# rainforest.net
KiCad netlist of a schematic drawn in EAGLE
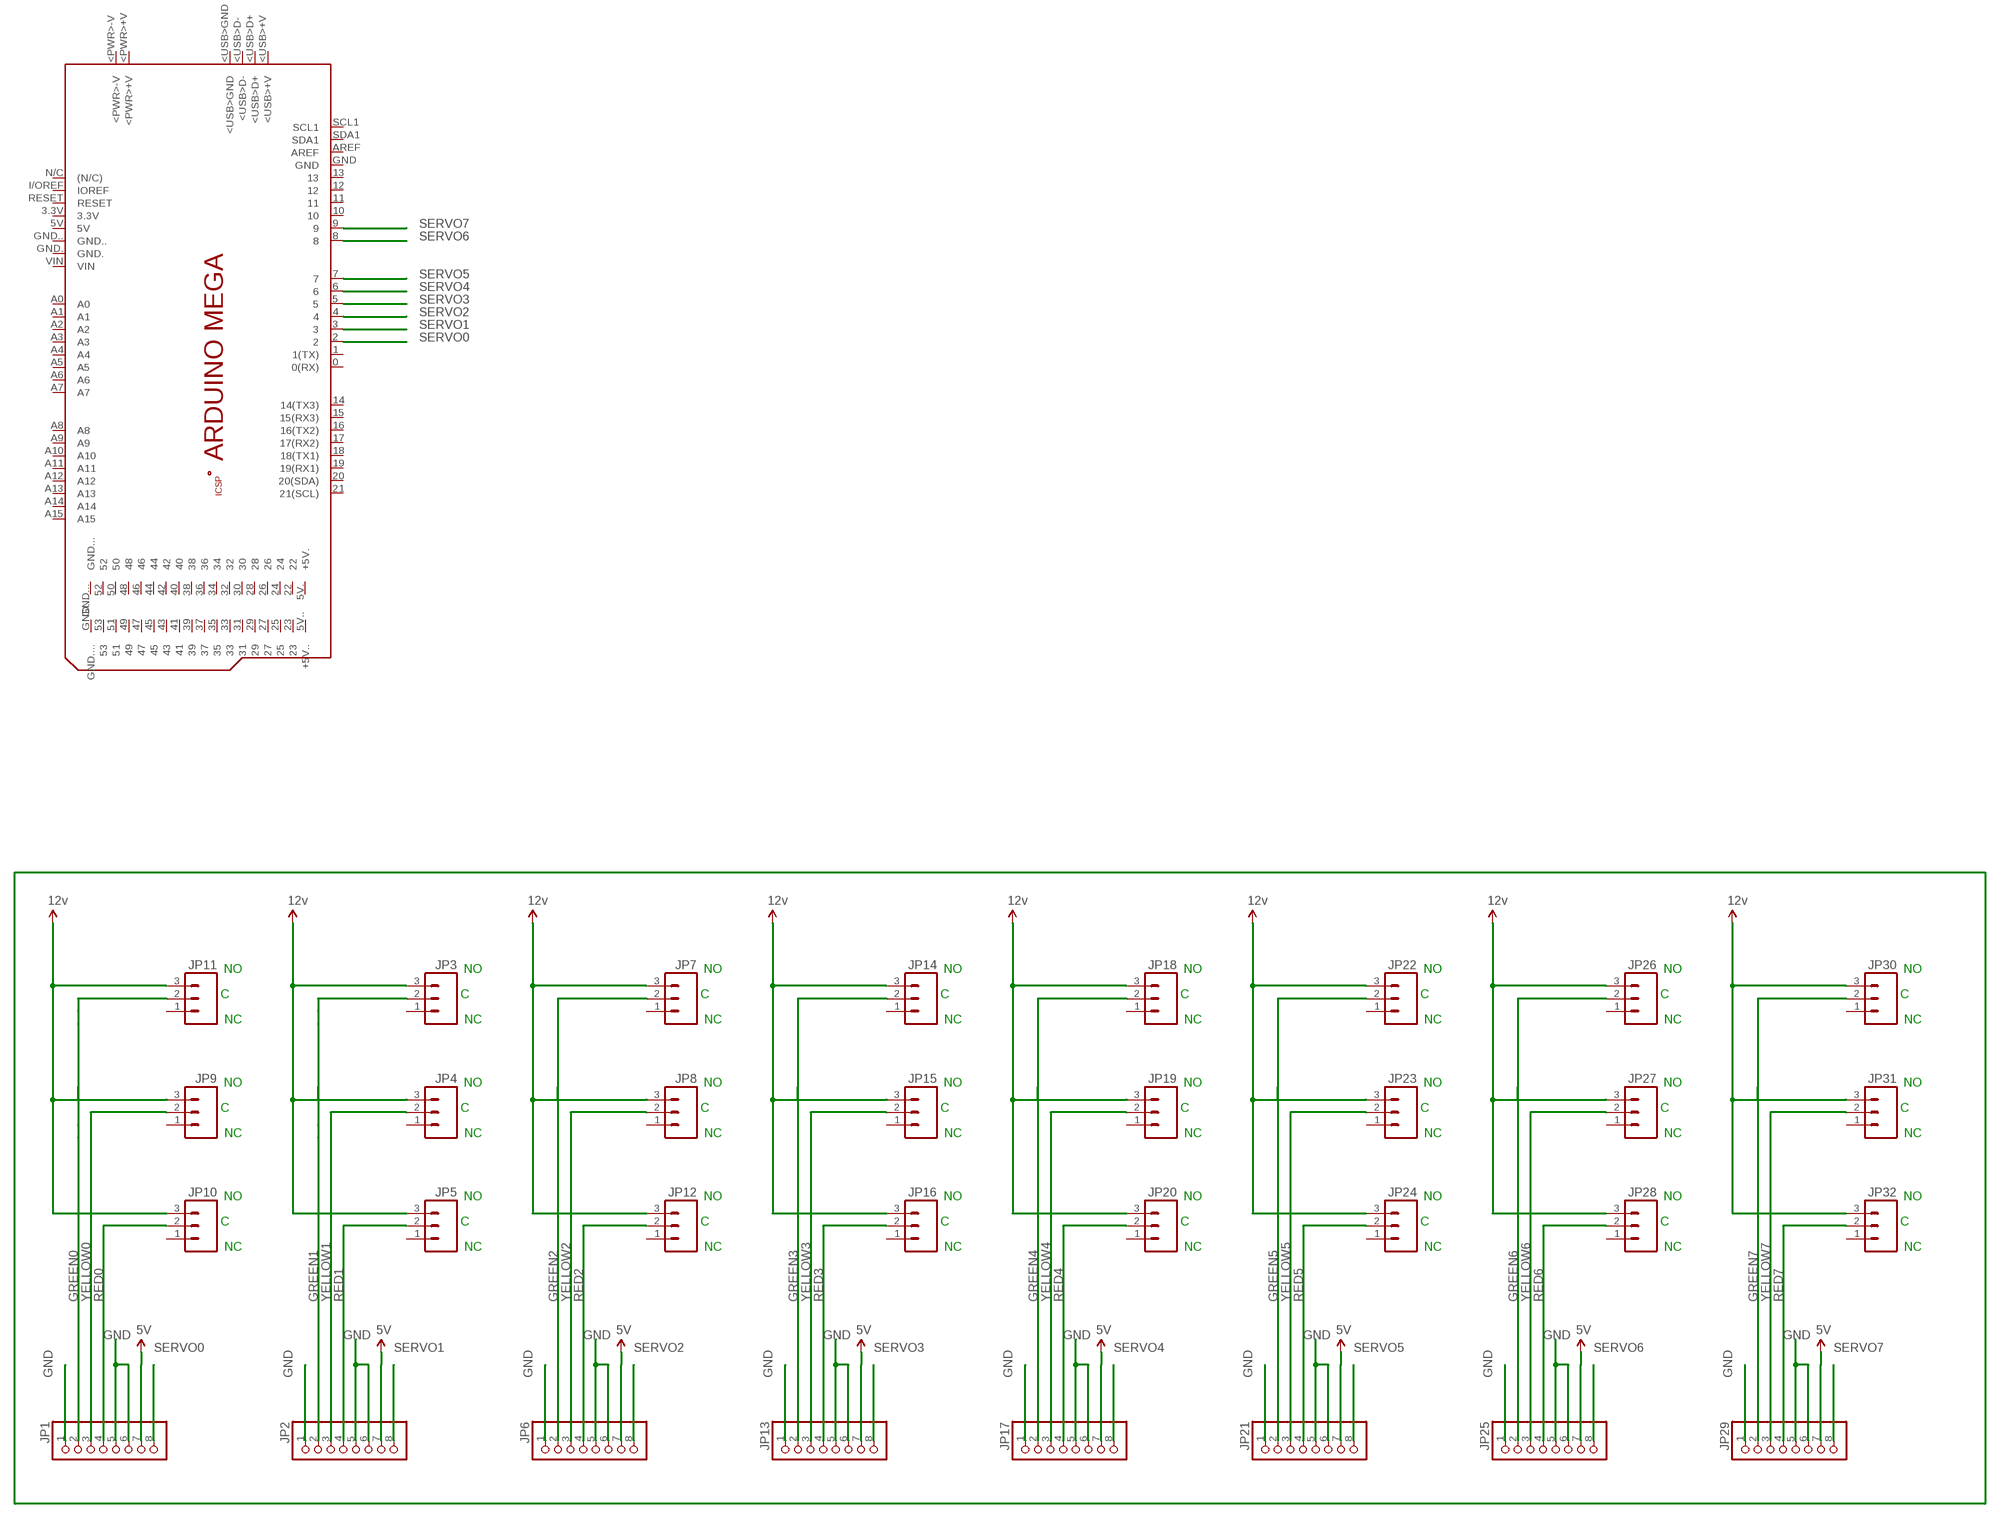
[diagram p0: schematic, sheet 1]

(export (version "E")
  (design (tool "Eeschema 10.0.6"))
  (components
    (comp (ref "JP1")
      (value "PINHD-1X8")
      (footprint "eagle-import:1X08")
      (fields (field (name "PARTNUMBER") "965"))
      (libsource (lib "eagle-import") (part "PINHD-1X8"))
    )
    (comp (ref "JP2")
      (value "PINHD-1X8")
      (footprint "eagle-import:1X08")
      (fields (field (name "PARTNUMBER") "965"))
      (libsource (lib "eagle-import") (part "PINHD-1X8"))
    )
    (comp (ref "JP3")
      (value "M03PTH")
      (footprint "eagle-import:1X03")
      (libsource (lib "eagle-import") (part "M03PTH"))
    )
    (comp (ref "JP4")
      (value "M03PTH")
      (footprint "eagle-import:1X03")
      (libsource (lib "eagle-import") (part "M03PTH"))
    )
    (comp (ref "JP5")
      (value "M03PTH")
      (footprint "eagle-import:1X03")
      (libsource (lib "eagle-import") (part "M03PTH"))
    )
    (comp (ref "JP6")
      (value "PINHD-1X8")
      (footprint "eagle-import:1X08")
      (fields (field (name "PARTNUMBER") "965"))
      (libsource (lib "eagle-import") (part "PINHD-1X8"))
    )
    (comp (ref "JP7")
      (value "M03PTH")
      (footprint "eagle-import:1X03")
      (libsource (lib "eagle-import") (part "M03PTH"))
    )
    (comp (ref "JP8")
      (value "M03PTH")
      (footprint "eagle-import:1X03")
      (libsource (lib "eagle-import") (part "M03PTH"))
    )
    (comp (ref "JP9")
      (value "M03PTH")
      (footprint "eagle-import:1X03")
      (libsource (lib "eagle-import") (part "M03PTH"))
    )
    (comp (ref "JP10")
      (value "M03PTH")
      (footprint "eagle-import:1X03")
      (libsource (lib "eagle-import") (part "M03PTH"))
    )
    (comp (ref "JP11")
      (value "M03PTH")
      (footprint "eagle-import:1X03")
      (libsource (lib "eagle-import") (part "M03PTH"))
    )
    (comp (ref "JP12")
      (value "M03PTH")
      (footprint "eagle-import:1X03")
      (libsource (lib "eagle-import") (part "M03PTH"))
    )
    (comp (ref "JP13")
      (value "PINHD-1X8")
      (footprint "eagle-import:1X08")
      (fields (field (name "PARTNUMBER") "965"))
      (libsource (lib "eagle-import") (part "PINHD-1X8"))
    )
    (comp (ref "JP14")
      (value "M03PTH")
      (footprint "eagle-import:1X03")
      (libsource (lib "eagle-import") (part "M03PTH"))
    )
    (comp (ref "JP15")
      (value "M03PTH")
      (footprint "eagle-import:1X03")
      (libsource (lib "eagle-import") (part "M03PTH"))
    )
    (comp (ref "JP16")
      (value "M03PTH")
      (footprint "eagle-import:1X03")
      (libsource (lib "eagle-import") (part "M03PTH"))
    )
    (comp (ref "JP17")
      (value "PINHD-1X8")
      (footprint "eagle-import:1X08")
      (fields (field (name "PARTNUMBER") "965"))
      (libsource (lib "eagle-import") (part "PINHD-1X8"))
    )
    (comp (ref "JP18")
      (value "M03PTH")
      (footprint "eagle-import:1X03")
      (libsource (lib "eagle-import") (part "M03PTH"))
    )
    (comp (ref "JP19")
      (value "M03PTH")
      (footprint "eagle-import:1X03")
      (libsource (lib "eagle-import") (part "M03PTH"))
    )
    (comp (ref "JP20")
      (value "M03PTH")
      (footprint "eagle-import:1X03")
      (libsource (lib "eagle-import") (part "M03PTH"))
    )
    (comp (ref "JP21")
      (value "PINHD-1X8")
      (footprint "eagle-import:1X08")
      (fields (field (name "PARTNUMBER") "965"))
      (libsource (lib "eagle-import") (part "PINHD-1X8"))
    )
    (comp (ref "JP22")
      (value "M03PTH")
      (footprint "eagle-import:1X03")
      (libsource (lib "eagle-import") (part "M03PTH"))
    )
    (comp (ref "JP23")
      (value "M03PTH")
      (footprint "eagle-import:1X03")
      (libsource (lib "eagle-import") (part "M03PTH"))
    )
    (comp (ref "JP24")
      (value "M03PTH")
      (footprint "eagle-import:1X03")
      (libsource (lib "eagle-import") (part "M03PTH"))
    )
    (comp (ref "JP25")
      (value "PINHD-1X8")
      (footprint "eagle-import:1X08")
      (fields (field (name "PARTNUMBER") "965"))
      (libsource (lib "eagle-import") (part "PINHD-1X8"))
    )
    (comp (ref "JP26")
      (value "M03PTH")
      (footprint "eagle-import:1X03")
      (libsource (lib "eagle-import") (part "M03PTH"))
    )
    (comp (ref "JP27")
      (value "M03PTH")
      (footprint "eagle-import:1X03")
      (libsource (lib "eagle-import") (part "M03PTH"))
    )
    (comp (ref "JP28")
      (value "M03PTH")
      (footprint "eagle-import:1X03")
      (libsource (lib "eagle-import") (part "M03PTH"))
    )
    (comp (ref "JP29")
      (value "PINHD-1X8")
      (footprint "eagle-import:1X08")
      (fields (field (name "PARTNUMBER") "965"))
      (libsource (lib "eagle-import") (part "PINHD-1X8"))
    )
    (comp (ref "JP30")
      (value "M03PTH")
      (footprint "eagle-import:1X03")
      (libsource (lib "eagle-import") (part "M03PTH"))
    )
    (comp (ref "JP31")
      (value "M03PTH")
      (footprint "eagle-import:1X03")
      (libsource (lib "eagle-import") (part "M03PTH"))
    )
    (comp (ref "JP32")
      (value "M03PTH")
      (footprint "eagle-import:1X03")
      (libsource (lib "eagle-import") (part "M03PTH"))
    )
    (comp (ref "PCB1")
      (value "ARDUINO_MEGA")
      (footprint "eagle-import:ARDUINO_MEGA")
      (libsource (lib "eagle-import") (part "ARDUINO_MEGA"))
    )
  )
  (nets
    (net (code "1") (name "/GND") (class "Default")
      (node (ref "JP1") (pin "1") (pinfunction "1_1") (pintype "passive"))
      (node (ref "JP1") (pin "5") (pinfunction "5_5") (pintype "passive"))
      (node (ref "JP1") (pin "6") (pinfunction "6_6") (pintype "passive"))
      (node (ref "JP13") (pin "1") (pinfunction "1_1") (pintype "passive"))
      (node (ref "JP13") (pin "5") (pinfunction "5_5") (pintype "passive"))
      (node (ref "JP13") (pin "6") (pinfunction "6_6") (pintype "passive"))
      (node (ref "JP17") (pin "1") (pinfunction "1_1") (pintype "passive"))
      (node (ref "JP17") (pin "5") (pinfunction "5_5") (pintype "passive"))
      (node (ref "JP17") (pin "6") (pinfunction "6_6") (pintype "passive"))
      (node (ref "JP2") (pin "1") (pinfunction "1_1") (pintype "passive"))
      (node (ref "JP2") (pin "5") (pinfunction "5_5") (pintype "passive"))
      (node (ref "JP2") (pin "6") (pinfunction "6_6") (pintype "passive"))
      (node (ref "JP21") (pin "1") (pinfunction "1_1") (pintype "passive"))
      (node (ref "JP21") (pin "5") (pinfunction "5_5") (pintype "passive"))
      (node (ref "JP21") (pin "6") (pinfunction "6_6") (pintype "passive"))
      (node (ref "JP25") (pin "1") (pinfunction "1_1") (pintype "passive"))
      (node (ref "JP25") (pin "5") (pinfunction "5_5") (pintype "passive"))
      (node (ref "JP25") (pin "6") (pinfunction "6_6") (pintype "passive"))
      (node (ref "JP29") (pin "1") (pinfunction "1_1") (pintype "passive"))
      (node (ref "JP29") (pin "5") (pinfunction "5_5") (pintype "passive"))
      (node (ref "JP29") (pin "6") (pinfunction "6_6") (pintype "passive"))
      (node (ref "JP6") (pin "1") (pinfunction "1_1") (pintype "passive"))
      (node (ref "JP6") (pin "5") (pinfunction "5_5") (pintype "passive"))
      (node (ref "JP6") (pin "6") (pinfunction "6_6") (pintype "passive"))
    )
    (net (code "2") (name "/GREEN0") (class "Default")
      (node (ref "JP1") (pin "2") (pinfunction "2_2") (pintype "passive"))
      (node (ref "JP11") (pin "2") (pinfunction "2_2") (pintype "passive"))
    )
    (net (code "3") (name "/GREEN1") (class "Default")
      (node (ref "JP2") (pin "2") (pinfunction "2_2") (pintype "passive"))
      (node (ref "JP3") (pin "2") (pinfunction "2_2") (pintype "passive"))
    )
    (net (code "4") (name "/GREEN2") (class "Default")
      (node (ref "JP6") (pin "2") (pinfunction "2_2") (pintype "passive"))
      (node (ref "JP7") (pin "2") (pinfunction "2_2") (pintype "passive"))
    )
    (net (code "5") (name "/GREEN3") (class "Default")
      (node (ref "JP13") (pin "2") (pinfunction "2_2") (pintype "passive"))
      (node (ref "JP14") (pin "2") (pinfunction "2_2") (pintype "passive"))
    )
    (net (code "6") (name "/GREEN4") (class "Default")
      (node (ref "JP17") (pin "2") (pinfunction "2_2") (pintype "passive"))
      (node (ref "JP18") (pin "2") (pinfunction "2_2") (pintype "passive"))
    )
    (net (code "7") (name "/GREEN5") (class "Default")
      (node (ref "JP21") (pin "2") (pinfunction "2_2") (pintype "passive"))
      (node (ref "JP22") (pin "2") (pinfunction "2_2") (pintype "passive"))
    )
    (net (code "8") (name "/GREEN6") (class "Default")
      (node (ref "JP25") (pin "2") (pinfunction "2_2") (pintype "passive"))
      (node (ref "JP26") (pin "2") (pinfunction "2_2") (pintype "passive"))
    )
    (net (code "9") (name "/GREEN7") (class "Default")
      (node (ref "JP29") (pin "2") (pinfunction "2_2") (pintype "passive"))
      (node (ref "JP30") (pin "2") (pinfunction "2_2") (pintype "passive"))
    )
    (net (code "10") (name "/RED0") (class "Default")
      (node (ref "JP1") (pin "4") (pinfunction "4_4") (pintype "passive"))
      (node (ref "JP10") (pin "2") (pinfunction "2_2") (pintype "passive"))
    )
    (net (code "11") (name "/RED1") (class "Default")
      (node (ref "JP2") (pin "4") (pinfunction "4_4") (pintype "passive"))
      (node (ref "JP5") (pin "2") (pinfunction "2_2") (pintype "passive"))
    )
    (net (code "12") (name "/RED2") (class "Default")
      (node (ref "JP12") (pin "2") (pinfunction "2_2") (pintype "passive"))
      (node (ref "JP6") (pin "4") (pinfunction "4_4") (pintype "passive"))
    )
    (net (code "13") (name "/RED3") (class "Default")
      (node (ref "JP13") (pin "4") (pinfunction "4_4") (pintype "passive"))
      (node (ref "JP16") (pin "2") (pinfunction "2_2") (pintype "passive"))
    )
    (net (code "14") (name "/RED4") (class "Default")
      (node (ref "JP17") (pin "4") (pinfunction "4_4") (pintype "passive"))
      (node (ref "JP20") (pin "2") (pinfunction "2_2") (pintype "passive"))
    )
    (net (code "15") (name "/RED5") (class "Default")
      (node (ref "JP21") (pin "4") (pinfunction "4_4") (pintype "passive"))
      (node (ref "JP24") (pin "2") (pinfunction "2_2") (pintype "passive"))
    )
    (net (code "16") (name "/RED6") (class "Default")
      (node (ref "JP25") (pin "4") (pinfunction "4_4") (pintype "passive"))
      (node (ref "JP28") (pin "2") (pinfunction "2_2") (pintype "passive"))
    )
    (net (code "17") (name "/RED7") (class "Default")
      (node (ref "JP29") (pin "4") (pinfunction "4_4") (pintype "passive"))
      (node (ref "JP32") (pin "2") (pinfunction "2_2") (pintype "passive"))
    )
    (net (code "18") (name "/SERVO0") (class "Default")
      (node (ref "JP1") (pin "8") (pinfunction "8_8") (pintype "passive"))
      (node (ref "PCB1") (pin "2") (pinfunction "2_2") (pintype "bidirectional"))
    )
    (net (code "19") (name "/SERVO1") (class "Default")
      (node (ref "JP2") (pin "8") (pinfunction "8_8") (pintype "passive"))
      (node (ref "PCB1") (pin "3") (pinfunction "3_3") (pintype "bidirectional"))
    )
    (net (code "20") (name "/SERVO2") (class "Default")
      (node (ref "JP6") (pin "8") (pinfunction "8_8") (pintype "passive"))
      (node (ref "PCB1") (pin "4") (pinfunction "4_4") (pintype "bidirectional"))
    )
    (net (code "21") (name "/SERVO3") (class "Default")
      (node (ref "JP13") (pin "8") (pinfunction "8_8") (pintype "passive"))
      (node (ref "PCB1") (pin "5") (pinfunction "5_5") (pintype "bidirectional"))
    )
    (net (code "22") (name "/SERVO4") (class "Default")
      (node (ref "JP17") (pin "8") (pinfunction "8_8") (pintype "passive"))
      (node (ref "PCB1") (pin "6") (pinfunction "6_6") (pintype "bidirectional"))
    )
    (net (code "23") (name "/SERVO5") (class "Default")
      (node (ref "JP21") (pin "8") (pinfunction "8_8") (pintype "passive"))
      (node (ref "PCB1") (pin "7") (pinfunction "7_7") (pintype "bidirectional"))
    )
    (net (code "24") (name "/SERVO6") (class "Default")
      (node (ref "JP25") (pin "8") (pinfunction "8_8") (pintype "passive"))
      (node (ref "PCB1") (pin "8") (pinfunction "8_8") (pintype "bidirectional"))
    )
    (net (code "25") (name "/SERVO7") (class "Default")
      (node (ref "JP29") (pin "8") (pinfunction "8_8") (pintype "passive"))
      (node (ref "PCB1") (pin "9") (pinfunction "9_9") (pintype "bidirectional"))
    )
    (net (code "26") (name "/YELLOW0") (class "Default")
      (node (ref "JP1") (pin "3") (pinfunction "3_3") (pintype "passive"))
      (node (ref "JP9") (pin "2") (pinfunction "2_2") (pintype "passive"))
    )
    (net (code "27") (name "/YELLOW1") (class "Default")
      (node (ref "JP2") (pin "3") (pinfunction "3_3") (pintype "passive"))
      (node (ref "JP4") (pin "2") (pinfunction "2_2") (pintype "passive"))
    )
    (net (code "28") (name "/YELLOW2") (class "Default")
      (node (ref "JP6") (pin "3") (pinfunction "3_3") (pintype "passive"))
      (node (ref "JP8") (pin "2") (pinfunction "2_2") (pintype "passive"))
    )
    (net (code "29") (name "/YELLOW3") (class "Default")
      (node (ref "JP13") (pin "3") (pinfunction "3_3") (pintype "passive"))
      (node (ref "JP15") (pin "2") (pinfunction "2_2") (pintype "passive"))
    )
    (net (code "30") (name "/YELLOW4") (class "Default")
      (node (ref "JP17") (pin "3") (pinfunction "3_3") (pintype "passive"))
      (node (ref "JP19") (pin "2") (pinfunction "2_2") (pintype "passive"))
    )
    (net (code "31") (name "/YELLOW5") (class "Default")
      (node (ref "JP21") (pin "3") (pinfunction "3_3") (pintype "passive"))
      (node (ref "JP23") (pin "2") (pinfunction "2_2") (pintype "passive"))
    )
    (net (code "32") (name "/YELLOW6") (class "Default")
      (node (ref "JP25") (pin "3") (pinfunction "3_3") (pintype "passive"))
      (node (ref "JP27") (pin "2") (pinfunction "2_2") (pintype "passive"))
    )
    (net (code "33") (name "/YELLOW7") (class "Default")
      (node (ref "JP29") (pin "3") (pinfunction "3_3") (pintype "passive"))
      (node (ref "JP31") (pin "2") (pinfunction "2_2") (pintype "passive"))
    )
    (net (code "34") (name "5V") (class "Default")
      (node (ref "JP1") (pin "7") (pinfunction "7_7") (pintype "passive"))
      (node (ref "JP13") (pin "7") (pinfunction "7_7") (pintype "passive"))
      (node (ref "JP17") (pin "7") (pinfunction "7_7") (pintype "passive"))
      (node (ref "JP2") (pin "7") (pinfunction "7_7") (pintype "passive"))
      (node (ref "JP21") (pin "7") (pinfunction "7_7") (pintype "passive"))
      (node (ref "JP25") (pin "7") (pinfunction "7_7") (pintype "passive"))
      (node (ref "JP29") (pin "7") (pinfunction "7_7") (pintype "passive"))
      (node (ref "JP6") (pin "7") (pinfunction "7_7") (pintype "passive"))
    )
    (net (code "35") (name "12v") (class "Default")
      (node (ref "JP10") (pin "3") (pinfunction "3_3") (pintype "passive"))
      (node (ref "JP11") (pin "3") (pinfunction "3_3") (pintype "passive"))
      (node (ref "JP12") (pin "3") (pinfunction "3_3") (pintype "passive"))
      (node (ref "JP14") (pin "3") (pinfunction "3_3") (pintype "passive"))
      (node (ref "JP15") (pin "3") (pinfunction "3_3") (pintype "passive"))
      (node (ref "JP16") (pin "3") (pinfunction "3_3") (pintype "passive"))
      (node (ref "JP18") (pin "3") (pinfunction "3_3") (pintype "passive"))
      (node (ref "JP19") (pin "3") (pinfunction "3_3") (pintype "passive"))
      (node (ref "JP20") (pin "3") (pinfunction "3_3") (pintype "passive"))
      (node (ref "JP22") (pin "3") (pinfunction "3_3") (pintype "passive"))
      (node (ref "JP23") (pin "3") (pinfunction "3_3") (pintype "passive"))
      (node (ref "JP24") (pin "3") (pinfunction "3_3") (pintype "passive"))
      (node (ref "JP26") (pin "3") (pinfunction "3_3") (pintype "passive"))
      (node (ref "JP27") (pin "3") (pinfunction "3_3") (pintype "passive"))
      (node (ref "JP28") (pin "3") (pinfunction "3_3") (pintype "passive"))
      (node (ref "JP3") (pin "3") (pinfunction "3_3") (pintype "passive"))
      (node (ref "JP30") (pin "3") (pinfunction "3_3") (pintype "passive"))
      (node (ref "JP31") (pin "3") (pinfunction "3_3") (pintype "passive"))
      (node (ref "JP32") (pin "3") (pinfunction "3_3") (pintype "passive"))
      (node (ref "JP4") (pin "3") (pinfunction "3_3") (pintype "passive"))
      (node (ref "JP5") (pin "3") (pinfunction "3_3") (pintype "passive"))
      (node (ref "JP7") (pin "3") (pinfunction "3_3") (pintype "passive"))
      (node (ref "JP8") (pin "3") (pinfunction "3_3") (pintype "passive"))
      (node (ref "JP9") (pin "3") (pinfunction "3_3") (pintype "passive"))
    )
    (net (code "36") (name "unconnected-(JP3-Pad1)") (class "Default")
      (node (ref "JP3") (pin "1") (pinfunction "1_1") (pintype "passive"))
    )
    (net (code "37") (name "unconnected-(JP4-Pad1)") (class "Default")
      (node (ref "JP4") (pin "1") (pinfunction "1_1") (pintype "passive"))
    )
    (net (code "38") (name "unconnected-(JP5-Pad1)") (class "Default")
      (node (ref "JP5") (pin "1") (pinfunction "1_1") (pintype "passive"))
    )
    (net (code "39") (name "unconnected-(JP7-Pad1)") (class "Default")
      (node (ref "JP7") (pin "1") (pinfunction "1_1") (pintype "passive"))
    )
    (net (code "40") (name "unconnected-(JP8-Pad1)") (class "Default")
      (node (ref "JP8") (pin "1") (pinfunction "1_1") (pintype "passive"))
    )
    (net (code "41") (name "unconnected-(JP9-Pad1)") (class "Default")
      (node (ref "JP9") (pin "1") (pinfunction "1_1") (pintype "passive"))
    )
    (net (code "42") (name "unconnected-(JP10-Pad1)") (class "Default")
      (node (ref "JP10") (pin "1") (pinfunction "1_1") (pintype "passive"))
    )
    (net (code "43") (name "unconnected-(JP11-Pad1)") (class "Default")
      (node (ref "JP11") (pin "1") (pinfunction "1_1") (pintype "passive"))
    )
    (net (code "44") (name "unconnected-(JP12-Pad1)") (class "Default")
      (node (ref "JP12") (pin "1") (pinfunction "1_1") (pintype "passive"))
    )
    (net (code "45") (name "unconnected-(JP14-Pad1)") (class "Default")
      (node (ref "JP14") (pin "1") (pinfunction "1_1") (pintype "passive"))
    )
    (net (code "46") (name "unconnected-(JP15-Pad1)") (class "Default")
      (node (ref "JP15") (pin "1") (pinfunction "1_1") (pintype "passive"))
    )
    (net (code "47") (name "unconnected-(JP16-Pad1)") (class "Default")
      (node (ref "JP16") (pin "1") (pinfunction "1_1") (pintype "passive"))
    )
    (net (code "48") (name "unconnected-(JP18-Pad1)") (class "Default")
      (node (ref "JP18") (pin "1") (pinfunction "1_1") (pintype "passive"))
    )
    (net (code "49") (name "unconnected-(JP19-Pad1)") (class "Default")
      (node (ref "JP19") (pin "1") (pinfunction "1_1") (pintype "passive"))
    )
    (net (code "50") (name "unconnected-(JP20-Pad1)") (class "Default")
      (node (ref "JP20") (pin "1") (pinfunction "1_1") (pintype "passive"))
    )
    (net (code "51") (name "unconnected-(JP22-Pad1)") (class "Default")
      (node (ref "JP22") (pin "1") (pinfunction "1_1") (pintype "passive"))
    )
    (net (code "52") (name "unconnected-(JP23-Pad1)") (class "Default")
      (node (ref "JP23") (pin "1") (pinfunction "1_1") (pintype "passive"))
    )
    (net (code "53") (name "unconnected-(JP24-Pad1)") (class "Default")
      (node (ref "JP24") (pin "1") (pinfunction "1_1") (pintype "passive"))
    )
    (net (code "54") (name "unconnected-(JP26-Pad1)") (class "Default")
      (node (ref "JP26") (pin "1") (pinfunction "1_1") (pintype "passive"))
    )
    (net (code "55") (name "unconnected-(JP27-Pad1)") (class "Default")
      (node (ref "JP27") (pin "1") (pinfunction "1_1") (pintype "passive"))
    )
    (net (code "56") (name "unconnected-(JP28-Pad1)") (class "Default")
      (node (ref "JP28") (pin "1") (pinfunction "1_1") (pintype "passive"))
    )
    (net (code "57") (name "unconnected-(JP30-Pad1)") (class "Default")
      (node (ref "JP30") (pin "1") (pinfunction "1_1") (pintype "passive"))
    )
    (net (code "58") (name "unconnected-(JP31-Pad1)") (class "Default")
      (node (ref "JP31") (pin "1") (pinfunction "1_1") (pintype "passive"))
    )
    (net (code "59") (name "unconnected-(JP32-Pad1)") (class "Default")
      (node (ref "JP32") (pin "1") (pinfunction "1_1") (pintype "passive"))
    )
    (net (code "60") (name "unconnected-(PCB1-(N{slash}C)-PadN{slash}C)") (class "Default")
      (node (ref "PCB1") (pin "N/C") (pinfunction "(N/C)_N/C") (pintype "bidirectional"))
    )
    (net (code "61") (name "unconnected-(PCB1-+5V.-Pad5V.)") (class "Default")
      (node (ref "PCB1") (pin "5V.") (pinfunction "+5V._5V.") (pintype "bidirectional"))
    )
    (net (code "62") (name "unconnected-(PCB1-+5V..-Pad5V..)") (class "Default")
      (node (ref "PCB1") (pin "5V..") (pinfunction "+5V.._5V..") (pintype "bidirectional"))
    )
    (net (code "63") (name "unconnected-(PCB1-0(RX)-Pad0)") (class "Default")
      (node (ref "PCB1") (pin "0") (pinfunction "0(RX)_0") (pintype "bidirectional"))
    )
    (net (code "64") (name "unconnected-(PCB1-1(TX)-Pad1)") (class "Default")
      (node (ref "PCB1") (pin "1") (pinfunction "1(TX)_1") (pintype "bidirectional"))
    )
    (net (code "65") (name "unconnected-(PCB1-14(TX3)-Pad14)") (class "Default")
      (node (ref "PCB1") (pin "14") (pinfunction "14(TX3)_14") (pintype "bidirectional"))
    )
    (net (code "66") (name "unconnected-(PCB1-15(RX3)-Pad15)") (class "Default")
      (node (ref "PCB1") (pin "15") (pinfunction "15(RX3)_15") (pintype "bidirectional"))
    )
    (net (code "67") (name "unconnected-(PCB1-16(TX2)-Pad16)") (class "Default")
      (node (ref "PCB1") (pin "16") (pinfunction "16(TX2)_16") (pintype "bidirectional"))
    )
    (net (code "68") (name "unconnected-(PCB1-17(RX2)-Pad17)") (class "Default")
      (node (ref "PCB1") (pin "17") (pinfunction "17(RX2)_17") (pintype "bidirectional"))
    )
    (net (code "69") (name "unconnected-(PCB1-18(TX1)-Pad18)") (class "Default")
      (node (ref "PCB1") (pin "18") (pinfunction "18(TX1)_18") (pintype "bidirectional"))
    )
    (net (code "70") (name "unconnected-(PCB1-19(RX1)-Pad19)") (class "Default")
      (node (ref "PCB1") (pin "19") (pinfunction "19(RX1)_19") (pintype "bidirectional"))
    )
    (net (code "71") (name "unconnected-(PCB1-20(SDA)-Pad20)") (class "Default")
      (node (ref "PCB1") (pin "20") (pinfunction "20(SDA)_20") (pintype "bidirectional"))
    )
    (net (code "72") (name "unconnected-(PCB1-21(SCL)-Pad21)") (class "Default")
      (node (ref "PCB1") (pin "21") (pinfunction "21(SCL)_21") (pintype "bidirectional"))
    )
    (net (code "73") (name "unconnected-(PCB1-IOREF-PadI{slash}OREF)") (class "Default")
      (node (ref "PCB1") (pin "I/OREF") (pinfunction "IOREF_I/OREF") (pintype "bidirectional"))
    )
    (net (code "74") (name "unconnected-(PCB1-Pad+5V_)") (class "Default")
      (node (ref "PCB1") (pin "+5V_") (pinfunction "+5V__+5V_") (pintype "bidirectional"))
    )
    (net (code "75") (name "unconnected-(PCB1-Pad3.3V)") (class "Default")
      (node (ref "PCB1") (pin "3.3V") (pinfunction "3.3V_3.3V") (pintype "bidirectional"))
    )
    (net (code "76") (name "unconnected-(PCB1-Pad5V)") (class "Default")
      (node (ref "PCB1") (pin "5V") (pinfunction "5V_5V") (pintype "bidirectional"))
    )
    (net (code "77") (name "unconnected-(PCB1-Pad10)") (class "Default")
      (node (ref "PCB1") (pin "10") (pinfunction "10_10") (pintype "bidirectional"))
    )
    (net (code "78") (name "unconnected-(PCB1-Pad11)") (class "Default")
      (node (ref "PCB1") (pin "11") (pinfunction "11_11") (pintype "bidirectional"))
    )
    (net (code "79") (name "unconnected-(PCB1-Pad12)") (class "Default")
      (node (ref "PCB1") (pin "12") (pinfunction "12_12") (pintype "bidirectional"))
    )
    (net (code "80") (name "unconnected-(PCB1-Pad13)") (class "Default")
      (node (ref "PCB1") (pin "13") (pinfunction "13_13") (pintype "bidirectional"))
    )
    (net (code "81") (name "unconnected-(PCB1-Pad22)") (class "Default")
      (node (ref "PCB1") (pin "22") (pinfunction "22_22") (pintype "bidirectional"))
    )
    (net (code "82") (name "unconnected-(PCB1-Pad23)") (class "Default")
      (node (ref "PCB1") (pin "23") (pinfunction "23_23") (pintype "bidirectional"))
    )
    (net (code "83") (name "unconnected-(PCB1-Pad24)") (class "Default")
      (node (ref "PCB1") (pin "24") (pinfunction "24_24") (pintype "bidirectional"))
    )
    (net (code "84") (name "unconnected-(PCB1-Pad25)") (class "Default")
      (node (ref "PCB1") (pin "25") (pinfunction "25_25") (pintype "bidirectional"))
    )
    (net (code "85") (name "unconnected-(PCB1-Pad26)") (class "Default")
      (node (ref "PCB1") (pin "26") (pinfunction "26_26") (pintype "bidirectional"))
    )
    (net (code "86") (name "unconnected-(PCB1-Pad27)") (class "Default")
      (node (ref "PCB1") (pin "27") (pinfunction "27_27") (pintype "bidirectional"))
    )
    (net (code "87") (name "unconnected-(PCB1-Pad28)") (class "Default")
      (node (ref "PCB1") (pin "28") (pinfunction "28_28") (pintype "bidirectional"))
    )
    (net (code "88") (name "unconnected-(PCB1-Pad29)") (class "Default")
      (node (ref "PCB1") (pin "29") (pinfunction "29_29") (pintype "bidirectional"))
    )
    (net (code "89") (name "unconnected-(PCB1-Pad30)") (class "Default")
      (node (ref "PCB1") (pin "30") (pinfunction "30_30") (pintype "bidirectional"))
    )
    (net (code "90") (name "unconnected-(PCB1-Pad31)") (class "Default")
      (node (ref "PCB1") (pin "31") (pinfunction "31_31") (pintype "bidirectional"))
    )
    (net (code "91") (name "unconnected-(PCB1-Pad32)") (class "Default")
      (node (ref "PCB1") (pin "32") (pinfunction "32_32") (pintype "bidirectional"))
    )
    (net (code "92") (name "unconnected-(PCB1-Pad33)") (class "Default")
      (node (ref "PCB1") (pin "33") (pinfunction "33_33") (pintype "bidirectional"))
    )
    (net (code "93") (name "unconnected-(PCB1-Pad34)") (class "Default")
      (node (ref "PCB1") (pin "34") (pinfunction "34_34") (pintype "bidirectional"))
    )
    (net (code "94") (name "unconnected-(PCB1-Pad35)") (class "Default")
      (node (ref "PCB1") (pin "35") (pinfunction "35_35") (pintype "bidirectional"))
    )
    (net (code "95") (name "unconnected-(PCB1-Pad36)") (class "Default")
      (node (ref "PCB1") (pin "36") (pinfunction "36_36") (pintype "bidirectional"))
    )
    (net (code "96") (name "unconnected-(PCB1-Pad37)") (class "Default")
      (node (ref "PCB1") (pin "37") (pinfunction "37_37") (pintype "bidirectional"))
    )
    (net (code "97") (name "unconnected-(PCB1-Pad38)") (class "Default")
      (node (ref "PCB1") (pin "38") (pinfunction "38_38") (pintype "bidirectional"))
    )
    (net (code "98") (name "unconnected-(PCB1-Pad39)") (class "Default")
      (node (ref "PCB1") (pin "39") (pinfunction "39_39") (pintype "bidirectional"))
    )
    (net (code "99") (name "unconnected-(PCB1-Pad40)") (class "Default")
      (node (ref "PCB1") (pin "40") (pinfunction "40_40") (pintype "bidirectional"))
    )
    (net (code "100") (name "unconnected-(PCB1-Pad41)") (class "Default")
      (node (ref "PCB1") (pin "41") (pinfunction "41_41") (pintype "bidirectional"))
    )
    (net (code "101") (name "unconnected-(PCB1-Pad42)") (class "Default")
      (node (ref "PCB1") (pin "42") (pinfunction "42_42") (pintype "bidirectional"))
    )
    (net (code "102") (name "unconnected-(PCB1-Pad43)") (class "Default")
      (node (ref "PCB1") (pin "43") (pinfunction "43_43") (pintype "bidirectional"))
    )
    (net (code "103") (name "unconnected-(PCB1-Pad44)") (class "Default")
      (node (ref "PCB1") (pin "44") (pinfunction "44_44") (pintype "bidirectional"))
    )
    (net (code "104") (name "unconnected-(PCB1-Pad45)") (class "Default")
      (node (ref "PCB1") (pin "45") (pinfunction "45_45") (pintype "bidirectional"))
    )
    (net (code "105") (name "unconnected-(PCB1-Pad46)") (class "Default")
      (node (ref "PCB1") (pin "46") (pinfunction "46_46") (pintype "bidirectional"))
    )
    (net (code "106") (name "unconnected-(PCB1-Pad47)") (class "Default")
      (node (ref "PCB1") (pin "47") (pinfunction "47_47") (pintype "bidirectional"))
    )
    (net (code "107") (name "unconnected-(PCB1-Pad48)") (class "Default")
      (node (ref "PCB1") (pin "48") (pinfunction "48_48") (pintype "bidirectional"))
    )
    (net (code "108") (name "unconnected-(PCB1-Pad49)") (class "Default")
      (node (ref "PCB1") (pin "49") (pinfunction "49_49") (pintype "bidirectional"))
    )
    (net (code "109") (name "unconnected-(PCB1-Pad50)") (class "Default")
      (node (ref "PCB1") (pin "50") (pinfunction "50_50") (pintype "bidirectional"))
    )
    (net (code "110") (name "unconnected-(PCB1-Pad51)") (class "Default")
      (node (ref "PCB1") (pin "51") (pinfunction "51_51") (pintype "bidirectional"))
    )
    (net (code "111") (name "unconnected-(PCB1-Pad52)") (class "Default")
      (node (ref "PCB1") (pin "52") (pinfunction "52_52") (pintype "bidirectional"))
    )
    (net (code "112") (name "unconnected-(PCB1-Pad53)") (class "Default")
      (node (ref "PCB1") (pin "53") (pinfunction "53_53") (pintype "bidirectional"))
    )
    (net (code "113") (name "unconnected-(PCB1-Pad<PWR>+V)") (class "Default")
      (node (ref "PCB1") (pin "<PWR>+V") (pinfunction "<PWR>+V_<PWR>+V") (pintype "no_connect"))
    )
    (net (code "114") (name "unconnected-(PCB1-Pad<PWR>-V)") (class "Default")
      (node (ref "PCB1") (pin "<PWR>-V") (pinfunction "<PWR>-V_<PWR>-V") (pintype "no_connect"))
    )
    (net (code "115") (name "unconnected-(PCB1-Pad<USB>+V)") (class "Default")
      (node (ref "PCB1") (pin "<USB>+V") (pinfunction "<USB>+V_<USB>+V") (pintype "no_connect"))
    )
    (net (code "116") (name "unconnected-(PCB1-Pad<USB>D+)") (class "Default")
      (node (ref "PCB1") (pin "<USB>D+") (pinfunction "<USB>D+_<USB>D+") (pintype "no_connect"))
    )
    (net (code "117") (name "unconnected-(PCB1-Pad<USB>D-)") (class "Default")
      (node (ref "PCB1") (pin "<USB>D-") (pinfunction "<USB>D-_<USB>D-") (pintype "no_connect"))
    )
    (net (code "118") (name "unconnected-(PCB1-Pad<USB>GND)") (class "Default")
      (node (ref "PCB1") (pin "<USB>GND") (pinfunction "<USB>GND_<USB>GND") (pintype "no_connect"))
    )
    (net (code "119") (name "unconnected-(PCB1-PadA0)") (class "Default")
      (node (ref "PCB1") (pin "A0") (pinfunction "A0_A0") (pintype "bidirectional"))
    )
    (net (code "120") (name "unconnected-(PCB1-PadA1)") (class "Default")
      (node (ref "PCB1") (pin "A1") (pinfunction "A1_A1") (pintype "bidirectional"))
    )
    (net (code "121") (name "unconnected-(PCB1-PadA2)") (class "Default")
      (node (ref "PCB1") (pin "A2") (pinfunction "A2_A2") (pintype "bidirectional"))
    )
    (net (code "122") (name "unconnected-(PCB1-PadA3)") (class "Default")
      (node (ref "PCB1") (pin "A3") (pinfunction "A3_A3") (pintype "bidirectional"))
    )
    (net (code "123") (name "unconnected-(PCB1-PadA4)") (class "Default")
      (node (ref "PCB1") (pin "A4") (pinfunction "A4_A4") (pintype "bidirectional"))
    )
    (net (code "124") (name "unconnected-(PCB1-PadA5)") (class "Default")
      (node (ref "PCB1") (pin "A5") (pinfunction "A5_A5") (pintype "bidirectional"))
    )
    (net (code "125") (name "unconnected-(PCB1-PadA6)") (class "Default")
      (node (ref "PCB1") (pin "A6") (pinfunction "A6_A6") (pintype "bidirectional"))
    )
    (net (code "126") (name "unconnected-(PCB1-PadA7)") (class "Default")
      (node (ref "PCB1") (pin "A7") (pinfunction "A7_A7") (pintype "bidirectional"))
    )
    (net (code "127") (name "unconnected-(PCB1-PadA8)") (class "Default")
      (node (ref "PCB1") (pin "A8") (pinfunction "A8_A8") (pintype "bidirectional"))
    )
    (net (code "128") (name "unconnected-(PCB1-PadA9)") (class "Default")
      (node (ref "PCB1") (pin "A9") (pinfunction "A9_A9") (pintype "bidirectional"))
    )
    (net (code "129") (name "unconnected-(PCB1-PadA10)") (class "Default")
      (node (ref "PCB1") (pin "A10") (pinfunction "A10_A10") (pintype "bidirectional"))
    )
    (net (code "130") (name "unconnected-(PCB1-PadA11)") (class "Default")
      (node (ref "PCB1") (pin "A11") (pinfunction "A11_A11") (pintype "bidirectional"))
    )
    (net (code "131") (name "unconnected-(PCB1-PadA12)") (class "Default")
      (node (ref "PCB1") (pin "A12") (pinfunction "A12_A12") (pintype "bidirectional"))
    )
    (net (code "132") (name "unconnected-(PCB1-PadA13)") (class "Default")
      (node (ref "PCB1") (pin "A13") (pinfunction "A13_A13") (pintype "bidirectional"))
    )
    (net (code "133") (name "unconnected-(PCB1-PadA14)") (class "Default")
      (node (ref "PCB1") (pin "A14") (pinfunction "A14_A14") (pintype "bidirectional"))
    )
    (net (code "134") (name "unconnected-(PCB1-PadA15)") (class "Default")
      (node (ref "PCB1") (pin "A15") (pinfunction "A15_A15") (pintype "bidirectional"))
    )
    (net (code "135") (name "unconnected-(PCB1-PadAREF)") (class "Default")
      (node (ref "PCB1") (pin "AREF") (pinfunction "AREF_AREF") (pintype "bidirectional"))
    )
    (net (code "136") (name "unconnected-(PCB1-PadGND)") (class "Default")
      (node (ref "PCB1") (pin "GND") (pinfunction "GND_GND") (pintype "bidirectional"))
    )
    (net (code "137") (name "unconnected-(PCB1-PadGND.)") (class "Default")
      (node (ref "PCB1") (pin "GND.") (pinfunction "GND._GND.") (pintype "bidirectional"))
    )
    (net (code "138") (name "unconnected-(PCB1-PadGND..)") (class "Default")
      (node (ref "PCB1") (pin "GND..") (pinfunction "GND.._GND..") (pintype "bidirectional"))
    )
    (net (code "139") (name "unconnected-(PCB1-PadGND...)") (class "Default")
      (node (ref "PCB1") (pin "GND...") (pinfunction "GND..._GND...") (pintype "bidirectional"))
    )
    (net (code "140") (name "unconnected-(PCB1-PadGND....)") (class "Default")
      (node (ref "PCB1") (pin "GND....") (pinfunction "GND...._GND....") (pintype "bidirectional"))
    )
    (net (code "141") (name "unconnected-(PCB1-PadGND__)") (class "Default")
      (node (ref "PCB1") (pin "GND__") (pinfunction "GND___GND__") (pintype "bidirectional"))
    )
    (net (code "142") (name "unconnected-(PCB1-PadMISO)") (class "Default")
      (node (ref "PCB1") (pin "MISO") (pinfunction "MISO_MISO") (pintype "bidirectional"))
    )
    (net (code "143") (name "unconnected-(PCB1-PadMOSI)") (class "Default")
      (node (ref "PCB1") (pin "MOSI") (pinfunction "MOSI_MOSI") (pintype "bidirectional"))
    )
    (net (code "144") (name "unconnected-(PCB1-PadRESET)") (class "Default")
      (node (ref "PCB1") (pin "RESET") (pinfunction "RESET_RESET") (pintype "bidirectional"))
    )
    (net (code "145") (name "unconnected-(PCB1-PadRESET.)") (class "Default")
      (node (ref "PCB1") (pin "RESET.") (pinfunction "RESET._RESET.") (pintype "bidirectional"))
    )
    (net (code "146") (name "unconnected-(PCB1-PadSCK)") (class "Default")
      (node (ref "PCB1") (pin "SCK") (pinfunction "SCK_SCK") (pintype "bidirectional"))
    )
    (net (code "147") (name "unconnected-(PCB1-PadSCL1)") (class "Default")
      (node (ref "PCB1") (pin "SCL1") (pinfunction "SCL1_SCL1") (pintype "bidirectional"))
    )
    (net (code "148") (name "unconnected-(PCB1-PadSDA1)") (class "Default")
      (node (ref "PCB1") (pin "SDA1") (pinfunction "SDA1_SDA1") (pintype "bidirectional"))
    )
    (net (code "149") (name "unconnected-(PCB1-PadVIN)") (class "Default")
      (node (ref "PCB1") (pin "VIN") (pinfunction "VIN_VIN") (pintype "bidirectional"))
    )
  )
)
